# openSX70_ALPHA_V6_4-20181011.net
KiCad netlist of a schematic drawn in EAGLE
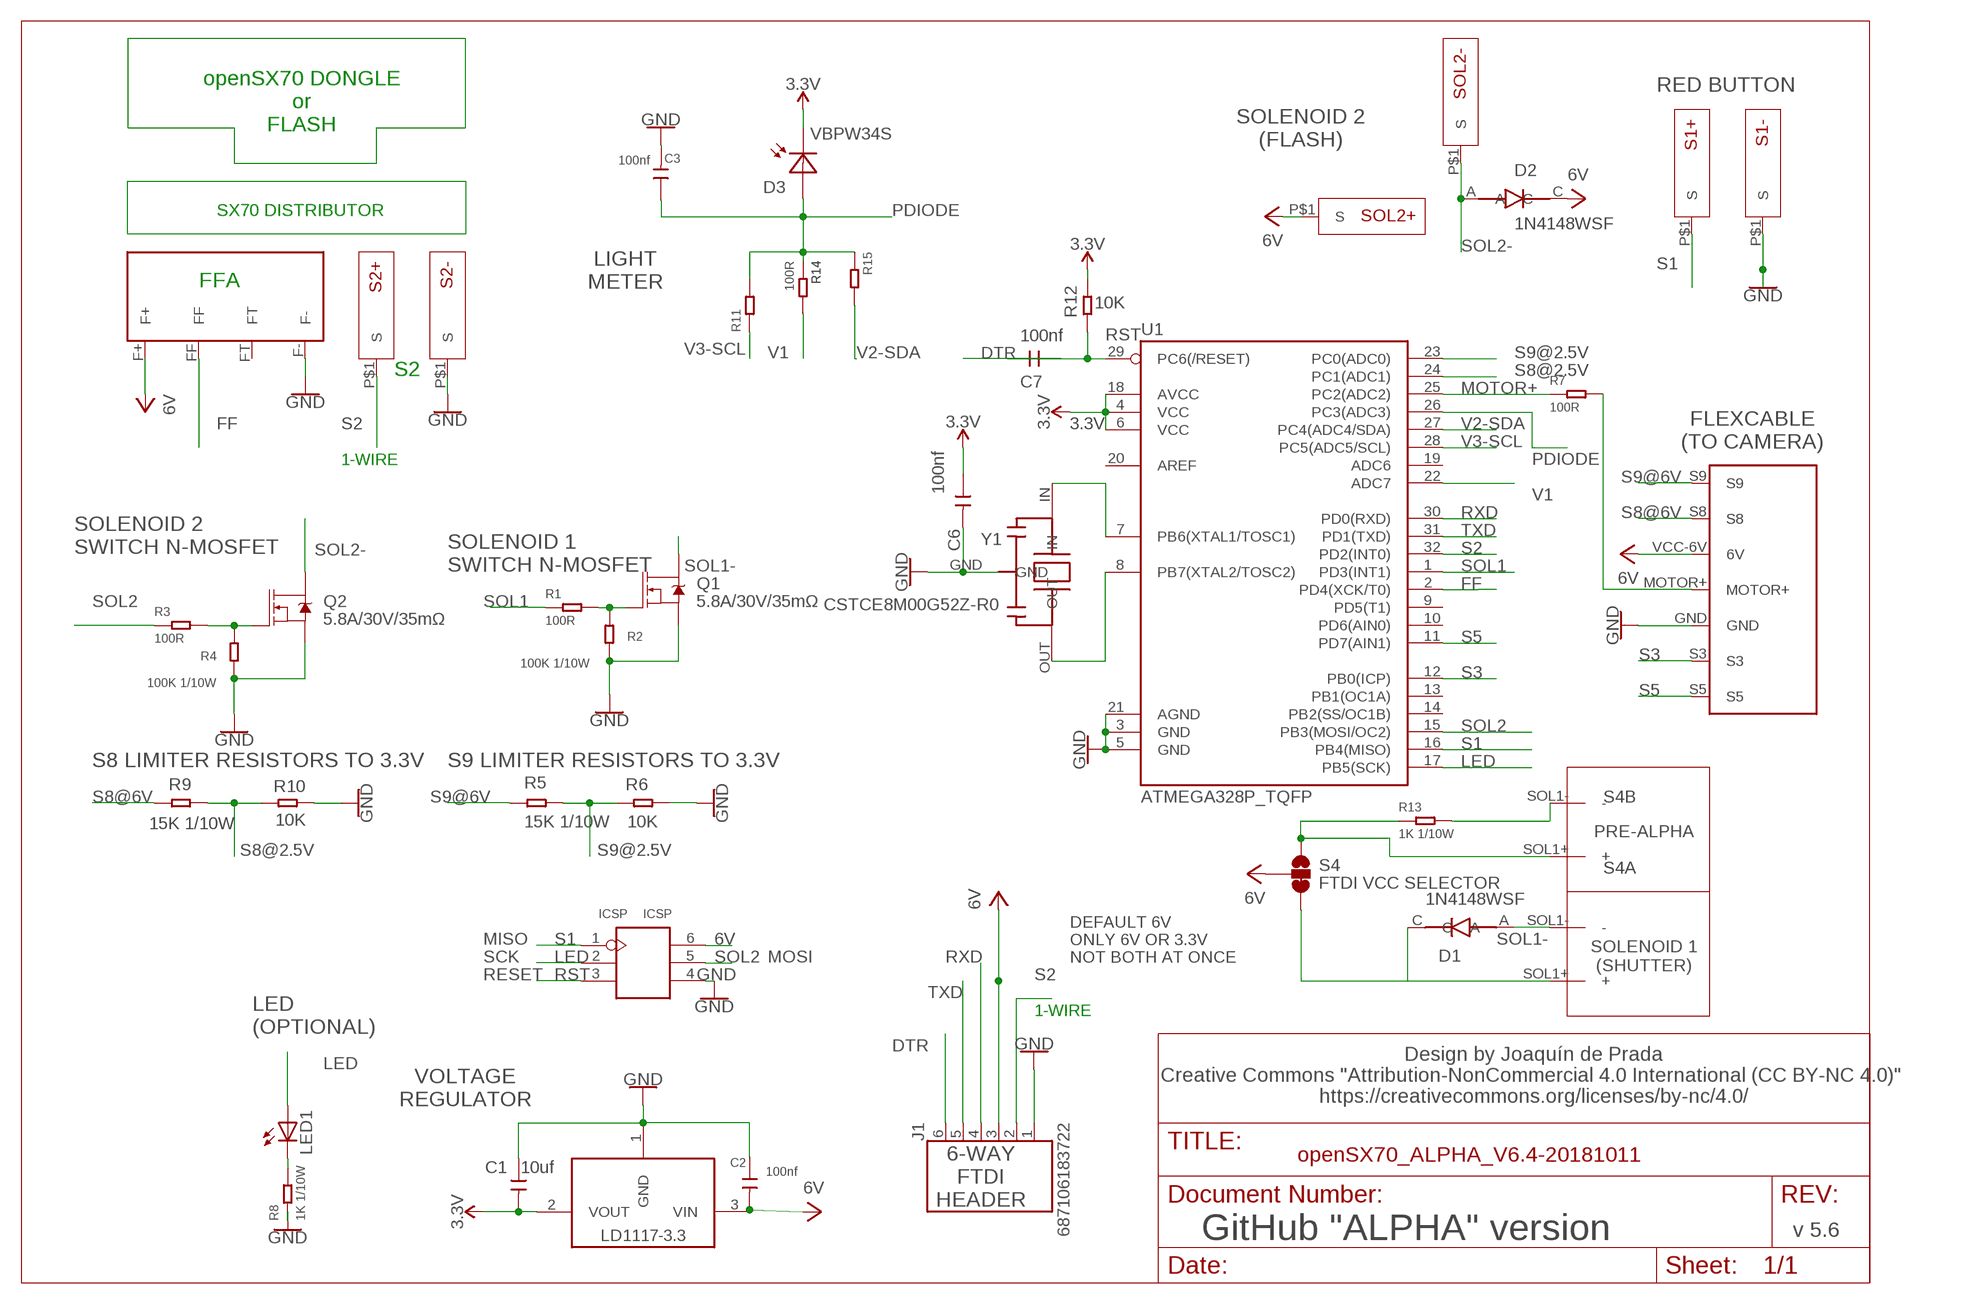
[diagram p0: schematic, sheet 1]

(export (version "E")
  (design (tool "Eeschema 10.0.6"))
  (components
    (comp (ref "C1")
      (value "10uf")
      (footprint "eagle-import:C0603")
      (fields (field (name "MPN") "CC0603KRX5R6BB106"))
      (libsource (lib "eagle-import") (part "CERAMIC-10UF-10V-10%-X5R(0603)"))
    )
    (comp (ref "C2")
      (value "100nf")
      (footprint "eagle-import:C0603")
      (fields (field (name "MPN") "CC0603KRX7R9BB104"))
      (libsource (lib "eagle-import") (part "CERAMIC-100NF-50V-10%-X7R(0603)"))
    )
    (comp (ref "C3")
      (value "100nf")
      (footprint "eagle-import:C0603")
      (fields (field (name "MPN") "CC0603KRX7R9BB104"))
      (libsource (lib "eagle-import") (part "CERAMIC-100NF-50V-10%-X7R(0603)"))
    )
    (comp (ref "C6")
      (value "100nf")
      (footprint "eagle-import:C0603")
      (fields (field (name "MPN") "CC0603KRX7R9BB104"))
      (libsource (lib "eagle-import") (part "CERAMIC-100NF-50V-10%-X7R(0603)"))
    )
    (comp (ref "C7")
      (value "100nf")
      (footprint "eagle-import:C0603")
      (fields (field (name "MPN") "CC0603KRX7R9BB104"))
      (libsource (lib "eagle-import") (part "CERAMIC-100NF-50V-10%-X7R(0603)"))
    )
    (comp (ref "D1")
      (value "1N4148WSF")
      (footprint "eagle-import:SODFL2512X100N")
      (fields (field (name "MANUFACTURER") "Fairchild Semiconductor"))
      (libsource (lib "eagle-import") (part "1N4148WS"))
    )
    (comp (ref "D2")
      (value "1N4148WSF")
      (footprint "eagle-import:SODFL2512X100N")
      (fields (field (name "MANUFACTURER") "Fairchild Semiconductor"))
      (libsource (lib "eagle-import") (part "1N4148WS"))
    )
    (comp (ref "D3")
      (value "VBPW34S")
      (footprint "eagle-import:SOD6439X130N")
      (fields (field (name "DIGI-KEY_PART_NUMBER") "751-1500-1-ND") (field (name "MF") "Vishay"))
      (libsource (lib "eagle-import") (part "VBPW34S"))
    )
    (comp (ref "ICSP")
      (value "ICSP")
      (footprint "eagle-import:H2X3-2.54")
      (libsource (lib "eagle-import") (part "ICSP"))
    )
    (comp (ref "J1")
      (value "687106183722")
      (footprint "eagle-import:687106183722")
      (fields (field (name "MF") "Wurth Electronics"))
      (libsource (lib "eagle-import") (part "687106183722"))
    )
    (comp (ref "LD11172.5V")
      (value "LD1117 2.5V")
      (footprint "eagle-import:SOT223")
      (fields (field (name "MF") "Advanced Monolithic Systems") (field (name "MP") "AMS1117-5.0"))
      (libsource (lib "eagle-import") (part "LD1117-3.3"))
    )
    (comp (ref "LED1")
      (value "LEDCHIPLED_0805")
      (footprint "eagle-import:CHIPLED_0805")
      (libsource (lib "eagle-import") (part "LEDCHIPLED_0805"))
    )
    (comp (ref "Q1")
      (value "5.8A/30V/35mΩ")
      (footprint "eagle-import:SOT23-3")
      (libsource (lib "eagle-import") (part "MOSFET-NCH-AO3404A"))
    )
    (comp (ref "Q2")
      (value "5.8A/30V/35mΩ")
      (footprint "eagle-import:SOT23-3")
      (libsource (lib "eagle-import") (part "MOSFET-NCH-AO3404A"))
    )
    (comp (ref "R1")
      (value "100R")
      (footprint "eagle-import:R0603")
      (fields (field (name "MPN") "RC0603JR-07100RL"))
      (libsource (lib "eagle-import") (part "SMD-RES-100R-5%-1/10W(0603)"))
    )
    (comp (ref "R2")
      (value "100K 1/10W")
      (footprint "eagle-import:R0603")
      (fields (field (name "MPN") "RC0603JR-07100KL"))
      (libsource (lib "eagle-import") (part "SMD-RES-100K-5%-1/10W(0603)"))
    )
    (comp (ref "R3")
      (value "100R")
      (footprint "eagle-import:R0603")
      (fields (field (name "MPN") "RC0603JR-07100RL"))
      (libsource (lib "eagle-import") (part "SMD-RES-100R-5%-1/10W(0603)"))
    )
    (comp (ref "R4")
      (value "100K 1/10W")
      (footprint "eagle-import:R0603")
      (fields (field (name "MPN") "RC0603JR-07100KL"))
      (libsource (lib "eagle-import") (part "SMD-RES-100K-5%-1/10W(0603)"))
    )
    (comp (ref "R5")
      (value "15K 1/10W")
      (footprint "eagle-import:R0603")
      (fields (field (name "MPN") "RC0603FR-0715KL"))
      (libsource (lib "eagle-import") (part "SMD-RES-15K-1%-1/10W(0603)"))
    )
    (comp (ref "R6")
      (value "10K")
      (footprint "eagle-import:R0603")
      (fields (field (name "MPN") "RC0603FR-0710KL"))
      (libsource (lib "eagle-import") (part "SMD-RES-10K-1%-1/10W(0603)"))
    )
    (comp (ref "R7")
      (value "100R")
      (footprint "eagle-import:R0603")
      (fields (field (name "MPN") "RC0603JR-07100RL"))
      (libsource (lib "eagle-import") (part "SMD-RES-100R-5%-1/10W(0603)"))
    )
    (comp (ref "R8")
      (value "1K 1/10W")
      (footprint "eagle-import:R0603")
      (fields (field (name "MPN") "RC0603JR-071KL"))
      (libsource (lib "eagle-import") (part "SMD-RES-1K-5%-1/10W(0603)"))
    )
    (comp (ref "R9")
      (value "15K 1/10W")
      (footprint "eagle-import:R0603")
      (fields (field (name "MPN") "RC0603FR-0715KL"))
      (libsource (lib "eagle-import") (part "SMD-RES-15K-1%-1/10W(0603)"))
    )
    (comp (ref "R10")
      (value "10K")
      (footprint "eagle-import:R0603")
      (fields (field (name "MPN") "RC0603FR-0710KL"))
      (libsource (lib "eagle-import") (part "SMD-RES-10K-1%-1/10W(0603)"))
    )
    (comp (ref "R11")
      (value "15K 1/10W")
      (footprint "eagle-import:R0603")
      (fields (field (name "MPN") "RC0603FR-0715KL"))
      (libsource (lib "eagle-import") (part "SMD-RES-15K-1%-1/10W(0603)"))
    )
    (comp (ref "R12")
      (value "10K")
      (footprint "eagle-import:R0603")
      (fields (field (name "MPN") "RC0603FR-0710KL"))
      (libsource (lib "eagle-import") (part "SMD-RES-10K-1%-1/10W(0603)"))
    )
    (comp (ref "R13")
      (value "1K 1/10W")
      (footprint "eagle-import:R0603")
      (fields (field (name "MPN") "RC0603JR-071KL"))
      (libsource (lib "eagle-import") (part "SMD-RES-1K-5%-1/10W(0603)"))
    )
    (comp (ref "R14")
      (value "100R")
      (footprint "eagle-import:R0603")
      (fields (field (name "MPN") "RC0603JR-07100RL"))
      (libsource (lib "eagle-import") (part "SMD-RES-100R-5%-1/10W(0603)"))
    )
    (comp (ref "R15")
      (value "100K 1/10W")
      (footprint "eagle-import:R0603")
      (fields (field (name "MPN") "RC0603JR-07100KL"))
      (libsource (lib "eagle-import") (part "SMD-RES-100K-5%-1/10W(0603)"))
    )
    (comp (ref "S1+")
      (value "SX70-S-PAD-NEW")
      (footprint "eagle-import:SX70-S-PAD2")
      (libsource (lib "eagle-import") (part "SX70-S-PAD-NEW"))
    )
    (comp (ref "S1-")
      (value "SX70-S-PAD-NEW")
      (footprint "eagle-import:SX70-S-PAD2")
      (libsource (lib "eagle-import") (part "SX70-S-PAD-NEW"))
    )
    (comp (ref "S2+")
      (value "SX70-S-PAD-NEW")
      (footprint "eagle-import:SX70-S-PAD2")
      (libsource (lib "eagle-import") (part "SX70-S-PAD-NEW"))
    )
    (comp (ref "S2-")
      (value "SX70-S-PAD-NEW")
      (footprint "eagle-import:SX70-S-PAD2")
      (libsource (lib "eagle-import") (part "SX70-S-PAD-NEW"))
    )
    (comp (ref "S4")
      (value "FTDI VCC SELECTOR")
      (footprint "eagle-import:SMT-JUMPER_3_1-NC_TRACE_SILK")
      (libsource (lib "eagle-import") (part "JUMPER-SMT_3_1-NC_TRACE_SILK"))
    )
    (comp (ref "SOL1")
      (value "SX70-SOLENOID1-2PADS")
      (footprint "eagle-import:SX70-SOLENOID1-2")
      (libsource (lib "eagle-import") (part "SX70-SOLENOID1-2PADS"))
    )
    (comp (ref "SOL2")
      (value "SX70-SOLENOID1-2PADS")
      (footprint "eagle-import:SX70-SOLENOID1-2")
      (libsource (lib "eagle-import") (part "SX70-SOLENOID1-2PADS"))
    )
    (comp (ref "SOL2+")
      (value "SX70-S-PAD-NEW")
      (footprint "eagle-import:SX70-S-PAD2")
      (libsource (lib "eagle-import") (part "SX70-S-PAD-NEW"))
    )
    (comp (ref "SOL2-")
      (value "SX70-S-PAD-NEW")
      (footprint "eagle-import:SX70-S-PAD2")
      (libsource (lib "eagle-import") (part "SX70-S-PAD-NEW"))
    )
    (comp (ref "U$1")
      (value "SX70-7-PAD")
      (footprint "eagle-import:SX70-7-PAD")
      (libsource (lib "eagle-import") (part "SX70-7-PAD"))
    )
    (comp (ref "U$2")
      (value "FFA")
      (footprint "eagle-import:FFA-PAD-PACKAGE")
      (libsource (lib "eagle-import") (part "SX70-FFA-PAD"))
    )
    (comp (ref "U1")
      (value "ATMEGA328P_TQFP")
      (footprint "eagle-import:TQFP32-08")
      (libsource (lib "eagle-import") (part "ATMEGA328P_TQFP"))
    )
    (comp (ref "Y1")
      (value "CSTCE8M00G52Z-R0")
      (footprint "eagle-import:CFP95P160X100-3N")
      (fields (field (name "MF") "Murata") (field (name "MP") "CSTCE16M0V53-R0"))
      (libsource (lib "eagle-import") (part "CSTCE16M0V53-R0"))
    )
  )
  (nets
    (net (code "1") (name "/DTR") (class "Default")
      (node (ref "C7") (pin "1") (pinfunction "1_1") (pintype "passive"))
      (node (ref "J1") (pin "6") (pinfunction "1_6") (pintype "passive"))
    )
    (net (code "2") (name "/FF") (class "Default")
      (node (ref "U$2") (pin "FF") (pinfunction "FF_FF") (pintype "bidirectional"))
      (node (ref "U1") (pin "2") (pinfunction "PD4(XCK/T0)_2") (pintype "bidirectional"))
    )
    (net (code "3") (name "/LED") (class "Default")
      (node (ref "ICSP") (pin "2") (pinfunction "SCK_2") (pintype "bidirectional"))
      (node (ref "LED1") (pin "A") (pinfunction "A_A") (pintype "passive"))
      (node (ref "U1") (pin "17") (pinfunction "PB5(SCK)_17") (pintype "bidirectional"))
    )
    (net (code "4") (name "/MOTOR+") (class "Default")
      (node (ref "R7") (pin "1") (pinfunction "1_1") (pintype "passive"))
      (node (ref "U1") (pin "25") (pinfunction "PC2(ADC2)_25") (pintype "bidirectional"))
    )
    (net (code "5") (name "/PDIODE") (class "Default")
      (node (ref "C3") (pin "1") (pinfunction "1_1") (pintype "passive"))
      (node (ref "D3") (pin "A") (pinfunction "A_A") (pintype "passive"))
      (node (ref "R11") (pin "2") (pinfunction "2_2") (pintype "passive"))
      (node (ref "R14") (pin "1") (pinfunction "1_1") (pintype "passive"))
      (node (ref "R15") (pin "1") (pinfunction "1_1") (pintype "passive"))
      (node (ref "U1") (pin "26") (pinfunction "PC3(ADC3)_26") (pintype "bidirectional"))
    )
    (net (code "6") (name "/RST") (class "Default")
      (node (ref "C7") (pin "2") (pinfunction "2_2") (pintype "passive"))
      (node (ref "ICSP") (pin "3") (pinfunction "RST_3") (pintype "bidirectional"))
      (node (ref "R12") (pin "1") (pinfunction "1_1") (pintype "passive"))
      (node (ref "U1") (pin "29") (pinfunction "PC6(/RESET)_29") (pintype "bidirectional"))
    )
    (net (code "7") (name "/RXD") (class "Default")
      (node (ref "J1") (pin "4") (pinfunction "3_4") (pintype "passive"))
      (node (ref "U1") (pin "30") (pinfunction "PD0(RXD)_30") (pintype "bidirectional"))
    )
    (net (code "8") (name "/S1") (class "Default")
      (node (ref "ICSP") (pin "1") (pinfunction "MISO_1") (pintype "bidirectional"))
      (node (ref "S1+") (pin "P$1") (pinfunction "S_P$1") (pintype "bidirectional"))
      (node (ref "U1") (pin "16") (pinfunction "PB4(MISO)_16") (pintype "bidirectional"))
    )
    (net (code "9") (name "/S2") (class "Default")
      (node (ref "J1") (pin "2") (pinfunction "5_2") (pintype "passive"))
      (node (ref "S2+") (pin "P$1") (pinfunction "S_P$1") (pintype "bidirectional"))
      (node (ref "U1") (pin "32") (pinfunction "PD2(INT0)_32") (pintype "bidirectional"))
    )
    (net (code "10") (name "/S3") (class "Default")
      (node (ref "U$1") (pin "S3") (pinfunction "S3_S3") (pintype "bidirectional"))
      (node (ref "U1") (pin "12") (pinfunction "PB0(ICP)_12") (pintype "bidirectional"))
    )
    (net (code "11") (name "/S5") (class "Default")
      (node (ref "U$1") (pin "S5") (pinfunction "S5_S5") (pintype "bidirectional"))
      (node (ref "U1") (pin "11") (pinfunction "PD7(AIN1)_11") (pintype "bidirectional"))
    )
    (net (code "12") (name "/S8@2.5V") (class "Default")
      (node (ref "R10") (pin "1") (pinfunction "1_1") (pintype "passive"))
      (node (ref "R9") (pin "2") (pinfunction "2_2") (pintype "passive"))
      (node (ref "U1") (pin "24") (pinfunction "PC1(ADC1)_24") (pintype "bidirectional"))
    )
    (net (code "13") (name "/S8@6V") (class "Default")
      (node (ref "R9") (pin "1") (pinfunction "1_1") (pintype "passive"))
      (node (ref "U$1") (pin "S8") (pinfunction "S8_S8") (pintype "bidirectional"))
    )
    (net (code "14") (name "/S9@2.5V") (class "Default")
      (node (ref "R5") (pin "2") (pinfunction "2_2") (pintype "passive"))
      (node (ref "R6") (pin "1") (pinfunction "1_1") (pintype "passive"))
      (node (ref "U1") (pin "23") (pinfunction "PC0(ADC0)_23") (pintype "bidirectional"))
    )
    (net (code "15") (name "/S9@6V") (class "Default")
      (node (ref "R5") (pin "1") (pinfunction "1_1") (pintype "passive"))
      (node (ref "U$1") (pin "S9") (pinfunction "S9_S9") (pintype "bidirectional"))
    )
    (net (code "16") (name "/SOL1") (class "Default")
      (node (ref "R1") (pin "1") (pinfunction "1_1") (pintype "passive"))
      (node (ref "U1") (pin "1") (pinfunction "PD3(INT1)_1") (pintype "bidirectional"))
    )
    (net (code "17") (name "/SOL1-") (class "Default")
      (node (ref "D1") (pin "A") (pinfunction "A_A") (pintype "passive"))
      (node (ref "Q1") (pin "3") (pinfunction "D_3") (pintype "bidirectional"))
      (node (ref "SOL1") (pin "SOL1-") (pinfunction "-_SOL1-") (pintype "bidirectional"))
    )
    (net (code "18") (name "/SOL2") (class "Default")
      (node (ref "ICSP") (pin "5") (pinfunction "MOSI_5") (pintype "bidirectional"))
      (node (ref "R3") (pin "1") (pinfunction "1_1") (pintype "passive"))
      (node (ref "U1") (pin "15") (pinfunction "PB3(MOSI/OC2)_15") (pintype "bidirectional"))
    )
    (net (code "19") (name "/SOL2-") (class "Default")
      (node (ref "D2") (pin "A") (pinfunction "A_A") (pintype "passive"))
      (node (ref "Q2") (pin "3") (pinfunction "D_3") (pintype "bidirectional"))
      (node (ref "SOL2-") (pin "P$1") (pinfunction "S_P$1") (pintype "bidirectional"))
    )
    (net (code "20") (name "/TXD") (class "Default")
      (node (ref "J1") (pin "5") (pinfunction "2_5") (pintype "passive"))
      (node (ref "U1") (pin "31") (pinfunction "PD1(TXD)_31") (pintype "bidirectional"))
    )
    (net (code "21") (name "/V1") (class "Default")
      (node (ref "R14") (pin "2") (pinfunction "2_2") (pintype "passive"))
      (node (ref "U1") (pin "22") (pinfunction "ADC7_22") (pintype "bidirectional"))
    )
    (net (code "22") (name "/V2-SDA") (class "Default")
      (node (ref "R15") (pin "2") (pinfunction "2_2") (pintype "passive"))
      (node (ref "U1") (pin "27") (pinfunction "PC4(ADC4/SDA)_27") (pintype "bidirectional"))
    )
    (net (code "23") (name "/V3-SCL") (class "Default")
      (node (ref "R11") (pin "1") (pinfunction "1_1") (pintype "passive"))
      (node (ref "U1") (pin "28") (pinfunction "PC5(ADC5/SCL)_28") (pintype "bidirectional"))
    )
    (net (code "24") (name "3.3V") (class "Default")
      (node (ref "C1") (pin "2") (pinfunction "2_2") (pintype "passive"))
      (node (ref "C6") (pin "1") (pinfunction "1_1") (pintype "passive"))
      (node (ref "D3") (pin "C") (pinfunction "C_C") (pintype "passive"))
      (node (ref "LD11172.5V") (pin "2") (pinfunction "VOUT_2") (pintype "bidirectional"))
      (node (ref "R12") (pin "2") (pinfunction "2_2") (pintype "passive"))
      (node (ref "U1") (pin "18") (pinfunction "AVCC_18") (pintype "bidirectional"))
      (node (ref "U1") (pin "4") (pinfunction "VCC_4") (pintype "bidirectional"))
      (node (ref "U1") (pin "6") (pinfunction "VCC_6") (pintype "bidirectional"))
    )
    (net (code "25") (name "6V") (class "Default")
      (node (ref "C2") (pin "2") (pinfunction "2_2") (pintype "passive"))
      (node (ref "D2") (pin "C") (pinfunction "C_C") (pintype "passive"))
      (node (ref "ICSP") (pin "6") (pinfunction "VCC_6") (pintype "bidirectional"))
      (node (ref "J1") (pin "3") (pinfunction "4_3") (pintype "passive"))
      (node (ref "LD11172.5V") (pin "3") (pinfunction "VIN_3") (pintype "bidirectional"))
      (node (ref "S4") (pin "2") (pinfunction "2_2") (pintype "passive"))
      (node (ref "SOL2+") (pin "P$1") (pinfunction "S_P$1") (pintype "bidirectional"))
      (node (ref "U$1") (pin "VCC-6V") (pinfunction "6V_VCC-6V") (pintype "bidirectional"))
      (node (ref "U$2") (pin "F+") (pinfunction "F+_F+") (pintype "bidirectional"))
    )
    (net (code "26") (name "GND") (class "Default")
      (node (ref "C1") (pin "1") (pinfunction "1_1") (pintype "passive"))
      (node (ref "C2") (pin "1") (pinfunction "1_1") (pintype "passive"))
      (node (ref "C3") (pin "2") (pinfunction "2_2") (pintype "passive"))
      (node (ref "C6") (pin "2") (pinfunction "2_2") (pintype "passive"))
      (node (ref "ICSP") (pin "4") (pinfunction "GND_4") (pintype "bidirectional"))
      (node (ref "J1") (pin "1") (pinfunction "6_1") (pintype "passive"))
      (node (ref "LD11172.5V") (pin "1") (pinfunction "GND_1") (pintype "bidirectional"))
      (node (ref "Q1") (pin "2") (pinfunction "S_2") (pintype "bidirectional"))
      (node (ref "Q2") (pin "2") (pinfunction "S_2") (pintype "bidirectional"))
      (node (ref "R10") (pin "2") (pinfunction "2_2") (pintype "passive"))
      (node (ref "R2") (pin "1") (pinfunction "1_1") (pintype "passive"))
      (node (ref "R4") (pin "1") (pinfunction "1_1") (pintype "passive"))
      (node (ref "R6") (pin "2") (pinfunction "2_2") (pintype "passive"))
      (node (ref "R8") (pin "1") (pinfunction "1_1") (pintype "passive"))
      (node (ref "S1-") (pin "P$1") (pinfunction "S_P$1") (pintype "bidirectional"))
      (node (ref "S2-") (pin "P$1") (pinfunction "S_P$1") (pintype "bidirectional"))
      (node (ref "U$1") (pin "GND") (pinfunction "GND_GND") (pintype "bidirectional"))
      (node (ref "U$2") (pin "F-") (pinfunction "F-_F-") (pintype "bidirectional"))
      (node (ref "U1") (pin "21") (pinfunction "AGND_21") (pintype "bidirectional"))
      (node (ref "U1") (pin "3") (pinfunction "GND_3") (pintype "bidirectional"))
      (node (ref "U1") (pin "5") (pinfunction "GND_5") (pintype "bidirectional"))
      (node (ref "Y1") (pin "GND") (pinfunction "GND_GND") (pintype "passive"))
    )
    (net (code "27") (name "Net-(LED1-PadC)") (class "Default")
      (node (ref "LED1") (pin "C") (pinfunction "C_C") (pintype "passive"))
      (node (ref "R8") (pin "2") (pinfunction "2_2") (pintype "passive"))
    )
    (net (code "28") (name "Net-(Q1-G)") (class "Default")
      (node (ref "Q1") (pin "1") (pinfunction "G_1") (pintype "bidirectional"))
      (node (ref "R1") (pin "2") (pinfunction "2_2") (pintype "passive"))
      (node (ref "R2") (pin "2") (pinfunction "2_2") (pintype "passive"))
    )
    (net (code "29") (name "Net-(Q2-G)") (class "Default")
      (node (ref "Q2") (pin "1") (pinfunction "G_1") (pintype "bidirectional"))
      (node (ref "R3") (pin "2") (pinfunction "2_2") (pintype "passive"))
      (node (ref "R4") (pin "2") (pinfunction "2_2") (pintype "passive"))
    )
    (net (code "30") (name "Net-(R7-Pad2)") (class "Default")
      (node (ref "R7") (pin "2") (pinfunction "2_2") (pintype "passive"))
      (node (ref "U$1") (pin "MOTOR+") (pinfunction "MOTOR+_MOTOR+") (pintype "bidirectional"))
    )
    (net (code "31") (name "Net-(SOL1-+)") (class "Default")
      (node (ref "D1") (pin "C") (pinfunction "C_C") (pintype "passive"))
      (node (ref "S4") (pin "3") (pinfunction "3_3") (pintype "passive"))
      (node (ref "SOL1") (pin "SOL1+") (pinfunction "+_SOL1+") (pintype "bidirectional"))
    )
    (net (code "32") (name "Net-(SOL2-+)") (class "Default")
      (node (ref "R13") (pin "1") (pinfunction "1_1") (pintype "passive"))
      (node (ref "S4") (pin "1") (pinfunction "1_1") (pintype "passive"))
      (node (ref "SOL2") (pin "SOL1+") (pinfunction "+_SOL1+") (pintype "bidirectional"))
    )
    (net (code "33") (name "Net-(SOL2--)") (class "Default")
      (node (ref "R13") (pin "2") (pinfunction "2_2") (pintype "passive"))
      (node (ref "SOL2") (pin "SOL1-") (pinfunction "-_SOL1-") (pintype "bidirectional"))
    )
    (net (code "34") (name "Net-(U1-PB6(XTAL1{slash}TOSC1))") (class "Default")
      (node (ref "U1") (pin "7") (pinfunction "PB6(XTAL1/TOSC1)_7") (pintype "bidirectional"))
      (node (ref "Y1") (pin "IN") (pinfunction "IN_IN") (pintype "input"))
    )
    (net (code "35") (name "Net-(U1-PB7(XTAL2{slash}TOSC2))") (class "Default")
      (node (ref "U1") (pin "8") (pinfunction "PB7(XTAL2/TOSC2)_8") (pintype "bidirectional"))
      (node (ref "Y1") (pin "OUT") (pinfunction "OUT_OUT") (pintype "output"))
    )
    (net (code "36") (name "unconnected-(U$2-PadFT)") (class "Default")
      (node (ref "U$2") (pin "FT") (pinfunction "FT_FT") (pintype "bidirectional"))
    )
    (net (code "37") (name "unconnected-(U1-ADC6-Pad19)") (class "Default")
      (node (ref "U1") (pin "19") (pinfunction "ADC6_19") (pintype "bidirectional"))
    )
    (net (code "38") (name "unconnected-(U1-AREF-Pad20)") (class "Default")
      (node (ref "U1") (pin "20") (pinfunction "AREF_20") (pintype "bidirectional"))
    )
    (net (code "39") (name "unconnected-(U1-PB1(OC1A)-Pad13)") (class "Default")
      (node (ref "U1") (pin "13") (pinfunction "PB1(OC1A)_13") (pintype "bidirectional"))
    )
    (net (code "40") (name "unconnected-(U1-PB2(SS{slash}OC1B)-Pad14)") (class "Default")
      (node (ref "U1") (pin "14") (pinfunction "PB2(SS/OC1B)_14") (pintype "bidirectional"))
    )
    (net (code "41") (name "unconnected-(U1-PD5(T1)-Pad9)") (class "Default")
      (node (ref "U1") (pin "9") (pinfunction "PD5(T1)_9") (pintype "bidirectional"))
    )
    (net (code "42") (name "unconnected-(U1-PD6(AIN0)-Pad10)") (class "Default")
      (node (ref "U1") (pin "10") (pinfunction "PD6(AIN0)_10") (pintype "bidirectional"))
    )
  )
)
